# HomeLight_230722.net
KiCad netlist of a schematic drawn in Altium Designer
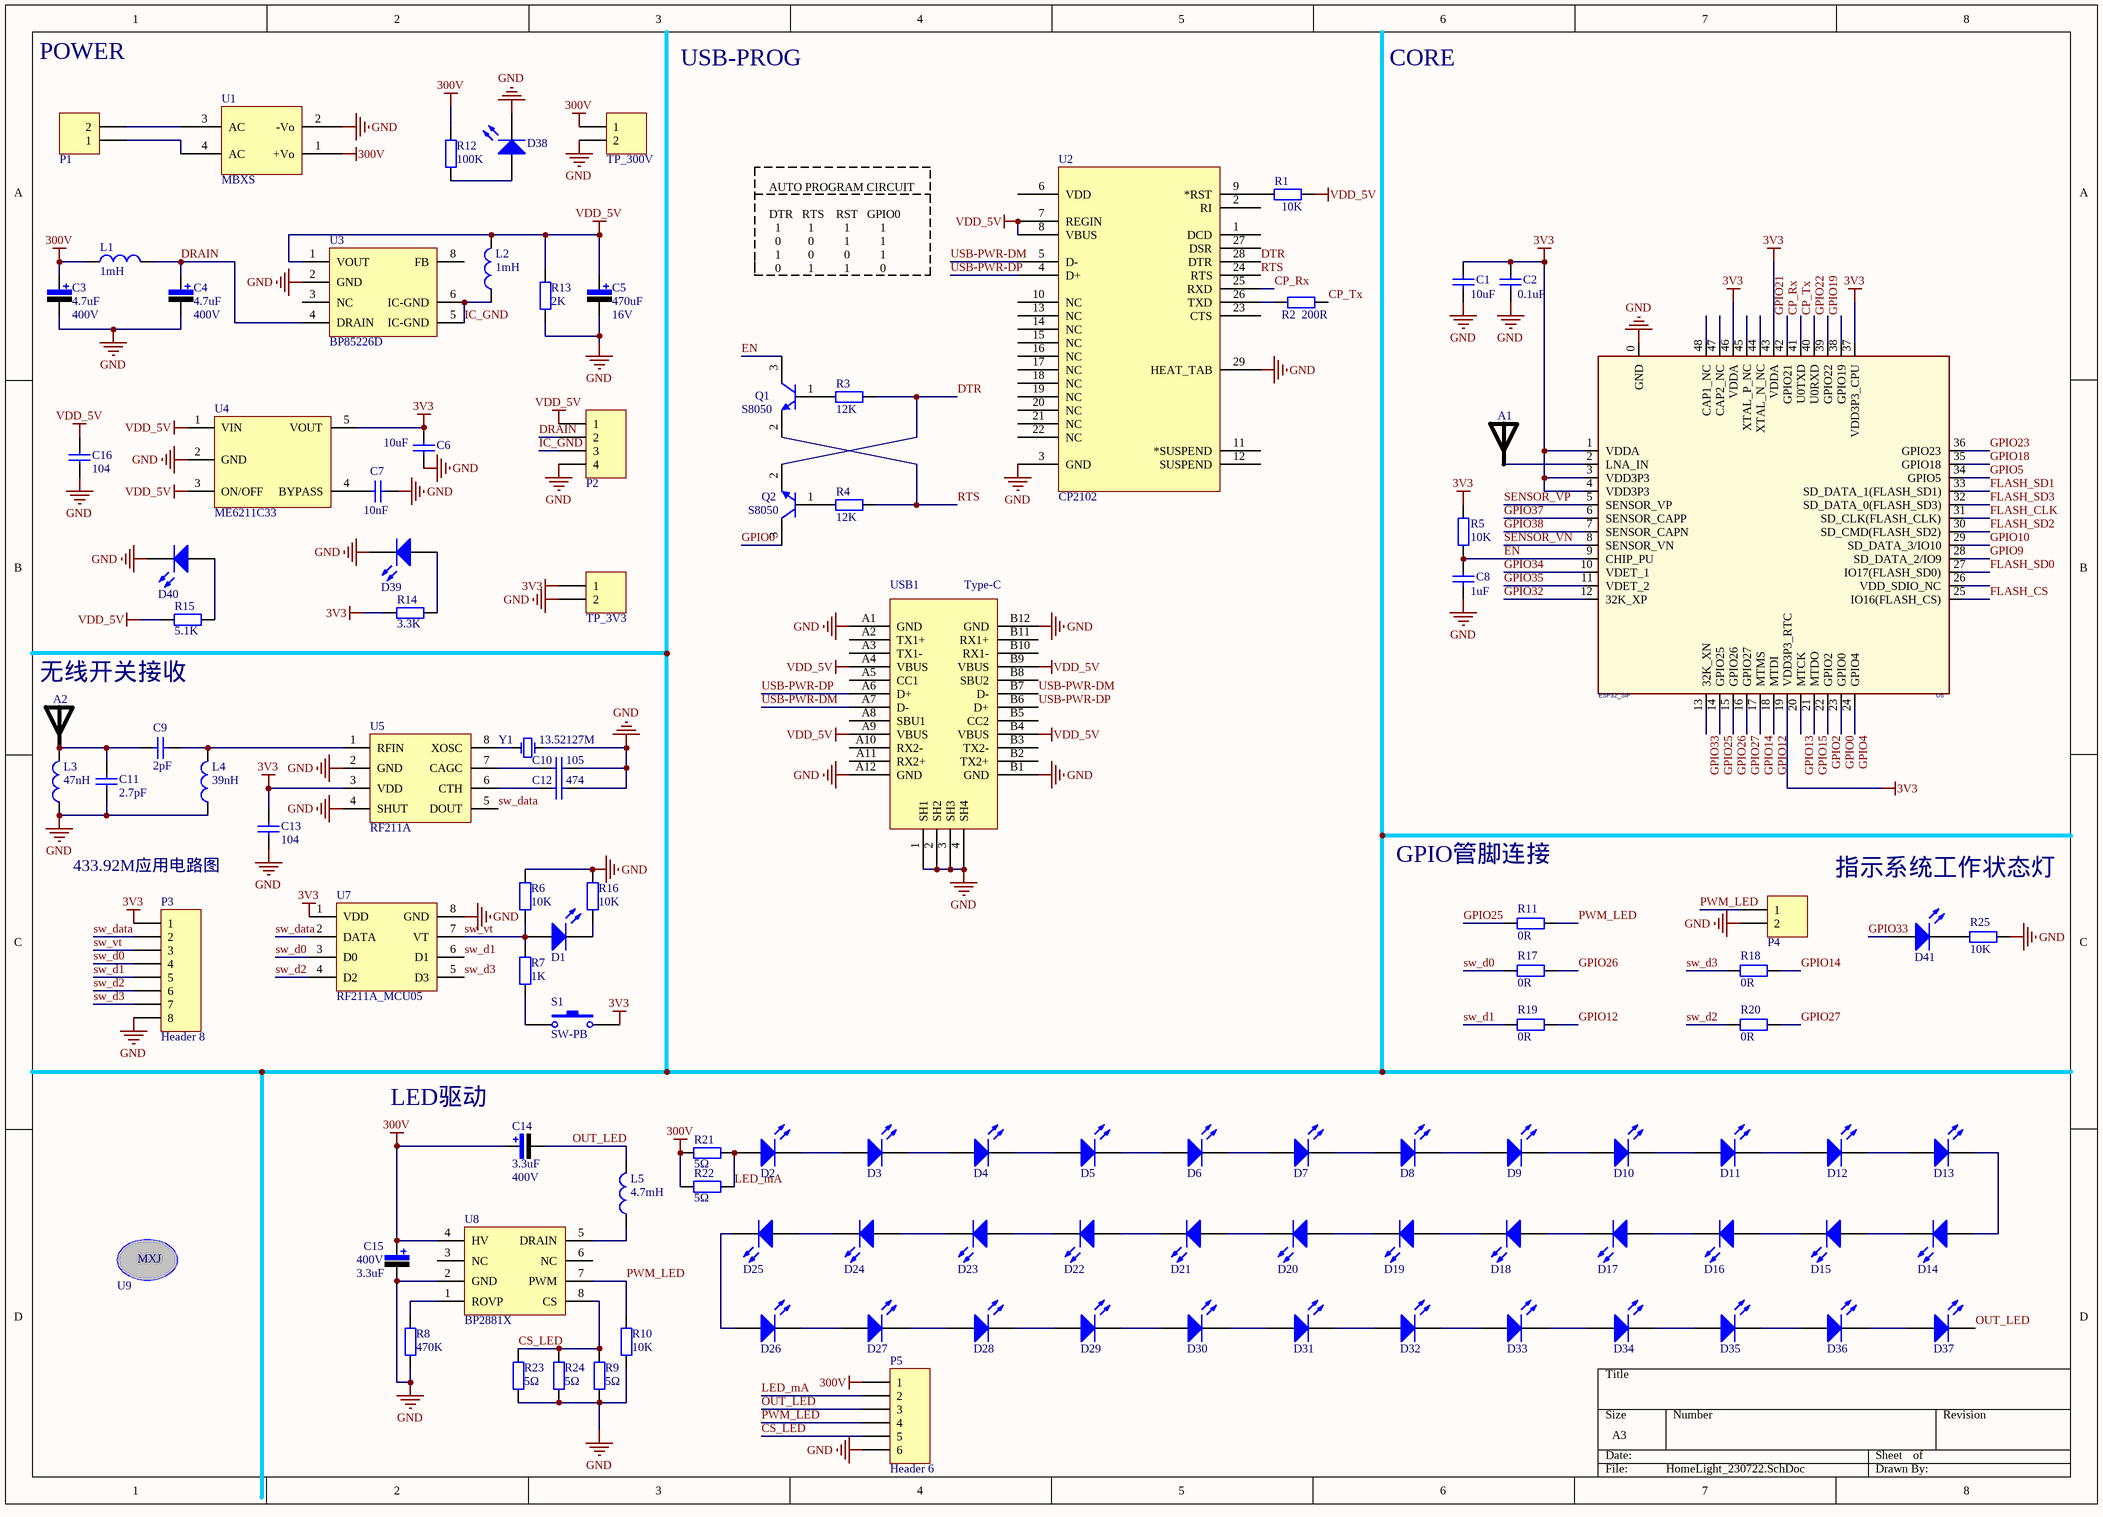
[diagram p0: HomeLight_230722.SchDoc]

(export (version "E")
  (design (tool "Eeschema 10.0.6"))
  (components
    (comp (ref "A1")
      (value "ANT")
      (footprint "ANT5020R2400")
      (libsource (lib "PCBSchlib_SEU_RobotLab") (part "ANT"))
    )
    (comp (ref "A2")
      (value "ANT")
      (footprint "PCBPcblib_SEU_RobotLab:ANT15030R433")
      (libsource (lib "PCBSchlib_SEU_RobotLab") (part "ANT"))
    )
    (comp (ref "C1")
      (value "10uF")
      (footprint "0603-2")
      (description "无极性电容")
      (fields (field (name "PUBLISHER") "Altium Limited"))
      (libsource (lib "PCBSchlib_SEU_RobotLab") (part "Cap"))
    )
    (comp (ref "C2")
      (value "0.1uF")
      (footprint "0603-2")
      (description "无极性电容")
      (fields (field (name "PUBLISHER") "Altium Limited"))
      (libsource (lib "PCBSchlib_SEU_RobotLab") (part "Cap"))
    )
    (comp (ref "C3")
      (value "4.7uF")
      (footprint "SMD-EC-F8")
      (description "极性电解电容")
      (fields
        (field (name "VOL") "400V")
        (field (name "Comment") "Cap Pol")
        (field (name "PUBLISHER") "Altium Limited")
      )
      (libsource (lib "PCBSchlib_SEU_RobotLab") (part "Cap Pol"))
    )
    (comp (ref "C4")
      (value "4.7uF")
      (footprint "SMD-EC-F8")
      (description "极性电解电容")
      (fields
        (field (name "VOL") "400V")
        (field (name "Comment") "Cap Pol")
        (field (name "PUBLISHER") "Altium Limited")
      )
      (libsource (lib "PCBSchlib_SEU_RobotLab") (part "Cap Pol"))
    )
    (comp (ref "C5")
      (value "470uF")
      (footprint "SMD-EC-F8")
      (description "极性电解电容")
      (fields
        (field (name "VOL") "16V")
        (field (name "Comment") "Cap Pol")
        (field (name "PUBLISHER") "Altium Limited")
      )
      (libsource (lib "PCBSchlib_SEU_RobotLab") (part "Cap Pol"))
    )
    (comp (ref "C6")
      (value "10uF")
      (footprint "0603-2")
      (description "无极性电容")
      (fields (field (name "PUBLISHER") "Altium Limited"))
      (libsource (lib "PCBSchlib_SEU_RobotLab") (part "Cap"))
    )
    (comp (ref "C7")
      (value "10nF")
      (footprint "0603-2")
      (description "无极性电容")
      (fields (field (name "PUBLISHER") "Altium Limited"))
      (libsource (lib "PCBSchlib_SEU_RobotLab") (part "Cap"))
    )
    (comp (ref "C8")
      (value "1uF")
      (footprint "0603-2")
      (description "无极性电容")
      (fields (field (name "PUBLISHER") "Altium Limited"))
      (libsource (lib "PCBSchlib_SEU_RobotLab") (part "Cap"))
    )
    (comp (ref "C9")
      (value "2pF")
      (footprint "0603-2")
      (description "无极性电容")
      (fields (field (name "Comment") "Cap") (field (name "PUBLISHER") "Altium Limited"))
      (libsource (lib "PCBSchlib_SEU_RobotLab") (part "Cap"))
    )
    (comp (ref "C10")
      (value "105")
      (footprint "0603-2")
      (description "无极性电容")
      (fields (field (name "Comment") "Cap") (field (name "PUBLISHER") "Altium Limited"))
      (libsource (lib "PCBSchlib_SEU_RobotLab") (part "Cap"))
    )
    (comp (ref "C11")
      (value "2.7pF")
      (footprint "0603-2")
      (description "无极性电容")
      (fields (field (name "Comment") "Cap") (field (name "PUBLISHER") "Altium Limited"))
      (libsource (lib "PCBSchlib_SEU_RobotLab") (part "Cap"))
    )
    (comp (ref "C12")
      (value "474")
      (footprint "0603-2")
      (description "无极性电容")
      (fields (field (name "Comment") "Cap") (field (name "PUBLISHER") "Altium Limited"))
      (libsource (lib "PCBSchlib_SEU_RobotLab") (part "Cap"))
    )
    (comp (ref "C13")
      (value "104")
      (footprint "0603-2")
      (description "无极性电容")
      (fields (field (name "Comment") "Cap") (field (name "PUBLISHER") "Altium Limited"))
      (libsource (lib "PCBSchlib_SEU_RobotLab") (part "Cap"))
    )
    (comp (ref "C14")
      (value "3.3uF")
      (footprint "SMD-EC-F8")
      (description "极性电解电容")
      (fields
        (field (name "VOL") "400V")
        (field (name "Comment") "Cap Pol")
        (field (name "PUBLISHER") "Altium Limited")
      )
      (libsource (lib "") (part "Cap Pol_1"))
    )
    (comp (ref "C15")
      (value "3.3uF")
      (footprint "SMD-EC-F8")
      (description "极性电解电容")
      (fields
        (field (name "VOL") "400V")
        (field (name "Comment") "Cap Pol")
        (field (name "PUBLISHER") "Altium Limited")
      )
      (libsource (lib "PCBSchlib_SEU_RobotLab") (part "Cap Pol"))
    )
    (comp (ref "C16")
      (value "104")
      (footprint "0603-2")
      (description "无极性电容")
      (fields (field (name "Comment") "Cap") (field (name "PUBLISHER") "Altium Limited"))
      (libsource (lib "PCBSchlib_SEU_RobotLab") (part "Cap"))
    )
    (comp (ref "D1")
      (value "LED0")
      (footprint "LED_0603")
      (description "发光二极管")
      (fields (field (name "PUBLISHER") "Altium Limited"))
      (libsource (lib "PCBSchlib_SEU_RobotLab") (part "LED0"))
    )
    (comp (ref "D2")
      (value "LED0")
      (footprint "PCBPcblib_SEU_RobotLab:LED-5730")
      (description "发光二极管")
      (fields (field (name "PUBLISHER") "Altium Limited"))
      (libsource (lib "PCBSchlib_SEU_RobotLab") (part "LED0"))
    )
    (comp (ref "D3")
      (value "LED0")
      (footprint "PCBPcblib_SEU_RobotLab:LED-5730")
      (description "发光二极管")
      (fields (field (name "PUBLISHER") "Altium Limited"))
      (libsource (lib "PCBSchlib_SEU_RobotLab") (part "LED0"))
    )
    (comp (ref "D4")
      (value "LED0")
      (footprint "PCBPcblib_SEU_RobotLab:LED-5730")
      (description "发光二极管")
      (fields (field (name "PUBLISHER") "Altium Limited"))
      (libsource (lib "PCBSchlib_SEU_RobotLab") (part "LED0"))
    )
    (comp (ref "D5")
      (value "LED0")
      (footprint "PCBPcblib_SEU_RobotLab:LED-5730")
      (description "发光二极管")
      (fields (field (name "PUBLISHER") "Altium Limited"))
      (libsource (lib "PCBSchlib_SEU_RobotLab") (part "LED0"))
    )
    (comp (ref "D6")
      (value "LED0")
      (footprint "PCBPcblib_SEU_RobotLab:LED-5730")
      (description "发光二极管")
      (fields (field (name "PUBLISHER") "Altium Limited"))
      (libsource (lib "PCBSchlib_SEU_RobotLab") (part "LED0"))
    )
    (comp (ref "D7")
      (value "LED0")
      (footprint "PCBPcblib_SEU_RobotLab:LED-5730")
      (description "发光二极管")
      (fields (field (name "PUBLISHER") "Altium Limited"))
      (libsource (lib "PCBSchlib_SEU_RobotLab") (part "LED0"))
    )
    (comp (ref "D8")
      (value "LED0")
      (footprint "PCBPcblib_SEU_RobotLab:LED-5730")
      (description "发光二极管")
      (fields (field (name "PUBLISHER") "Altium Limited"))
      (libsource (lib "PCBSchlib_SEU_RobotLab") (part "LED0"))
    )
    (comp (ref "D9")
      (value "LED0")
      (footprint "PCBPcblib_SEU_RobotLab:LED-5730")
      (description "发光二极管")
      (fields (field (name "PUBLISHER") "Altium Limited"))
      (libsource (lib "PCBSchlib_SEU_RobotLab") (part "LED0"))
    )
    (comp (ref "D10")
      (value "LED0")
      (footprint "PCBPcblib_SEU_RobotLab:LED-5730")
      (description "发光二极管")
      (fields (field (name "PUBLISHER") "Altium Limited"))
      (libsource (lib "PCBSchlib_SEU_RobotLab") (part "LED0"))
    )
    (comp (ref "D11")
      (value "LED0")
      (footprint "PCBPcblib_SEU_RobotLab:LED-5730")
      (description "发光二极管")
      (fields (field (name "PUBLISHER") "Altium Limited"))
      (libsource (lib "PCBSchlib_SEU_RobotLab") (part "LED0"))
    )
    (comp (ref "D12")
      (value "LED0")
      (footprint "PCBPcblib_SEU_RobotLab:LED-5730")
      (description "发光二极管")
      (fields (field (name "PUBLISHER") "Altium Limited"))
      (libsource (lib "PCBSchlib_SEU_RobotLab") (part "LED0"))
    )
    (comp (ref "D13")
      (value "LED0")
      (footprint "PCBPcblib_SEU_RobotLab:LED-5730")
      (description "发光二极管")
      (fields (field (name "PUBLISHER") "Altium Limited"))
      (libsource (lib "PCBSchlib_SEU_RobotLab") (part "LED0"))
    )
    (comp (ref "D14")
      (value "LED0")
      (footprint "PCBPcblib_SEU_RobotLab:LED-5730")
      (description "发光二极管")
      (fields (field (name "PUBLISHER") "Altium Limited"))
      (libsource (lib "PCBSchlib_SEU_RobotLab") (part "LED0"))
    )
    (comp (ref "D15")
      (value "LED0")
      (footprint "PCBPcblib_SEU_RobotLab:LED-5730")
      (description "发光二极管")
      (fields (field (name "PUBLISHER") "Altium Limited"))
      (libsource (lib "PCBSchlib_SEU_RobotLab") (part "LED0"))
    )
    (comp (ref "D16")
      (value "LED0")
      (footprint "PCBPcblib_SEU_RobotLab:LED-5730")
      (description "发光二极管")
      (fields (field (name "PUBLISHER") "Altium Limited"))
      (libsource (lib "PCBSchlib_SEU_RobotLab") (part "LED0"))
    )
    (comp (ref "D17")
      (value "LED0")
      (footprint "PCBPcblib_SEU_RobotLab:LED-5730")
      (description "发光二极管")
      (fields (field (name "PUBLISHER") "Altium Limited"))
      (libsource (lib "PCBSchlib_SEU_RobotLab") (part "LED0"))
    )
    (comp (ref "D18")
      (value "LED0")
      (footprint "PCBPcblib_SEU_RobotLab:LED-5730")
      (description "发光二极管")
      (fields (field (name "PUBLISHER") "Altium Limited"))
      (libsource (lib "PCBSchlib_SEU_RobotLab") (part "LED0"))
    )
    (comp (ref "D19")
      (value "LED0")
      (footprint "PCBPcblib_SEU_RobotLab:LED-5730")
      (description "发光二极管")
      (fields (field (name "PUBLISHER") "Altium Limited"))
      (libsource (lib "PCBSchlib_SEU_RobotLab") (part "LED0"))
    )
    (comp (ref "D20")
      (value "LED0")
      (footprint "PCBPcblib_SEU_RobotLab:LED-5730")
      (description "发光二极管")
      (fields (field (name "PUBLISHER") "Altium Limited"))
      (libsource (lib "PCBSchlib_SEU_RobotLab") (part "LED0"))
    )
    (comp (ref "D21")
      (value "LED0")
      (footprint "PCBPcblib_SEU_RobotLab:LED-5730")
      (description "发光二极管")
      (fields (field (name "PUBLISHER") "Altium Limited"))
      (libsource (lib "PCBSchlib_SEU_RobotLab") (part "LED0"))
    )
    (comp (ref "D22")
      (value "LED0")
      (footprint "PCBPcblib_SEU_RobotLab:LED-5730")
      (description "发光二极管")
      (fields (field (name "PUBLISHER") "Altium Limited"))
      (libsource (lib "PCBSchlib_SEU_RobotLab") (part "LED0"))
    )
    (comp (ref "D23")
      (value "LED0")
      (footprint "PCBPcblib_SEU_RobotLab:LED-5730")
      (description "发光二极管")
      (fields (field (name "PUBLISHER") "Altium Limited"))
      (libsource (lib "PCBSchlib_SEU_RobotLab") (part "LED0"))
    )
    (comp (ref "D24")
      (value "LED0")
      (footprint "PCBPcblib_SEU_RobotLab:LED-5730")
      (description "发光二极管")
      (fields (field (name "PUBLISHER") "Altium Limited"))
      (libsource (lib "PCBSchlib_SEU_RobotLab") (part "LED0"))
    )
    (comp (ref "D25")
      (value "LED0")
      (footprint "PCBPcblib_SEU_RobotLab:LED-5730")
      (description "发光二极管")
      (fields (field (name "PUBLISHER") "Altium Limited"))
      (libsource (lib "PCBSchlib_SEU_RobotLab") (part "LED0"))
    )
    (comp (ref "D26")
      (value "LED0")
      (footprint "PCBPcblib_SEU_RobotLab:LED-5730")
      (description "发光二极管")
      (fields (field (name "PUBLISHER") "Altium Limited"))
      (libsource (lib "PCBSchlib_SEU_RobotLab") (part "LED0"))
    )
    (comp (ref "D27")
      (value "LED0")
      (footprint "PCBPcblib_SEU_RobotLab:LED-5730")
      (description "发光二极管")
      (fields (field (name "PUBLISHER") "Altium Limited"))
      (libsource (lib "PCBSchlib_SEU_RobotLab") (part "LED0"))
    )
    (comp (ref "D28")
      (value "LED0")
      (footprint "PCBPcblib_SEU_RobotLab:LED-5730")
      (description "发光二极管")
      (fields (field (name "PUBLISHER") "Altium Limited"))
      (libsource (lib "PCBSchlib_SEU_RobotLab") (part "LED0"))
    )
    (comp (ref "D29")
      (value "LED0")
      (footprint "PCBPcblib_SEU_RobotLab:LED-5730")
      (description "发光二极管")
      (fields (field (name "PUBLISHER") "Altium Limited"))
      (libsource (lib "PCBSchlib_SEU_RobotLab") (part "LED0"))
    )
    (comp (ref "D30")
      (value "LED0")
      (footprint "PCBPcblib_SEU_RobotLab:LED-5730")
      (description "发光二极管")
      (fields (field (name "PUBLISHER") "Altium Limited"))
      (libsource (lib "PCBSchlib_SEU_RobotLab") (part "LED0"))
    )
    (comp (ref "D31")
      (value "LED0")
      (footprint "PCBPcblib_SEU_RobotLab:LED-5730")
      (description "发光二极管")
      (fields (field (name "PUBLISHER") "Altium Limited"))
      (libsource (lib "PCBSchlib_SEU_RobotLab") (part "LED0"))
    )
    (comp (ref "D32")
      (value "LED0")
      (footprint "PCBPcblib_SEU_RobotLab:LED-5730")
      (description "发光二极管")
      (fields (field (name "PUBLISHER") "Altium Limited"))
      (libsource (lib "PCBSchlib_SEU_RobotLab") (part "LED0"))
    )
    (comp (ref "D33")
      (value "LED0")
      (footprint "PCBPcblib_SEU_RobotLab:LED-5730")
      (description "发光二极管")
      (fields (field (name "PUBLISHER") "Altium Limited"))
      (libsource (lib "PCBSchlib_SEU_RobotLab") (part "LED0"))
    )
    (comp (ref "D34")
      (value "LED0")
      (footprint "PCBPcblib_SEU_RobotLab:LED-5730")
      (description "发光二极管")
      (fields (field (name "PUBLISHER") "Altium Limited"))
      (libsource (lib "PCBSchlib_SEU_RobotLab") (part "LED0"))
    )
    (comp (ref "D35")
      (value "LED0")
      (footprint "PCBPcblib_SEU_RobotLab:LED-5730")
      (description "发光二极管")
      (fields (field (name "PUBLISHER") "Altium Limited"))
      (libsource (lib "PCBSchlib_SEU_RobotLab") (part "LED0"))
    )
    (comp (ref "D36")
      (value "LED0")
      (footprint "PCBPcblib_SEU_RobotLab:LED-5730")
      (description "发光二极管")
      (fields (field (name "PUBLISHER") "Altium Limited"))
      (libsource (lib "PCBSchlib_SEU_RobotLab") (part "LED0"))
    )
    (comp (ref "D37")
      (value "LED0")
      (footprint "PCBPcblib_SEU_RobotLab:LED-5730")
      (description "发光二极管")
      (fields (field (name "PUBLISHER") "Altium Limited"))
      (libsource (lib "PCBSchlib_SEU_RobotLab") (part "LED0"))
    )
    (comp (ref "D38")
      (value "LED0")
      (footprint "LED_0603")
      (description "发光二极管")
      (fields (field (name "PUBLISHER") "Altium Limited"))
      (libsource (lib "PCBSchlib_SEU_RobotLab") (part "LED0"))
    )
    (comp (ref "D39")
      (value "LED0")
      (footprint "LED_0603")
      (description "发光二极管")
      (fields (field (name "PUBLISHER") "Altium Limited"))
      (libsource (lib "PCBSchlib_SEU_RobotLab") (part "LED0"))
    )
    (comp (ref "D40")
      (value "LED0")
      (footprint "LED_0603")
      (description "发光二极管")
      (fields (field (name "PUBLISHER") "Altium Limited"))
      (libsource (lib "PCBSchlib_SEU_RobotLab") (part "LED0"))
    )
    (comp (ref "D41")
      (value "LED0")
      (footprint "LED_0603")
      (description "发光二极管")
      (fields (field (name "PUBLISHER") "Altium Limited"))
      (libsource (lib "PCBSchlib_SEU_RobotLab") (part "LED0"))
    )
    (comp (ref "L1")
      (value "1mH")
      (footprint "PCBPcblib_SEU_RobotLab:CD54")
      (description "电感")
      (fields (field (name "Comment") "Inductor") (field (name "PUBLISHER") "Altium Limited"))
      (libsource (lib "PCBSchlib_SEU_RobotLab") (part "Inductor"))
    )
    (comp (ref "L2")
      (value "1mH")
      (footprint "PCBPcblib_SEU_RobotLab:CD54")
      (description "电感")
      (fields (field (name "Comment") "Inductor") (field (name "PUBLISHER") "Altium Limited"))
      (libsource (lib "PCBSchlib_SEU_RobotLab") (part "Inductor"))
    )
    (comp (ref "L3")
      (value "47nH")
      (footprint "PCBPcblib_SEU_RobotLab:0603-1")
      (description "电感")
      (fields (field (name "Comment") "Inductor") (field (name "PUBLISHER") "Altium Limited"))
      (libsource (lib "PCBSchlib_SEU_RobotLab") (part "Inductor"))
    )
    (comp (ref "L4")
      (value "39nH")
      (footprint "PCBPcblib_SEU_RobotLab:0603-1")
      (description "电感")
      (fields (field (name "Comment") "Inductor") (field (name "PUBLISHER") "Altium Limited"))
      (libsource (lib "PCBSchlib_SEU_RobotLab") (part "Inductor"))
    )
    (comp (ref "L5")
      (value "4.7mH")
      (footprint "PCBPcblib_SEU_RobotLab:CD54")
      (description "电感")
      (fields (field (name "Comment") "Inductor") (field (name "PUBLISHER") "Altium Limited"))
      (libsource (lib "PCBSchlib_SEU_RobotLab") (part "Inductor"))
    )
    (comp (ref "P1")
      (value "Header 2")
      (footprint "PCBPcblib_SEU_RobotLab:HDR2X1_焊接版")
      (description "接插件")
      (fields (field (name "PUBLISHER") "Altium Limited"))
      (libsource (lib "") (part "Header 2_1"))
    )
    (comp (ref "P2")
      (value "Header 4")
      (footprint "HDR4X1_2.54")
      (description "接插件")
      (fields (field (name "PUBLISHER") "Altium Limited"))
      (libsource (lib "PCBSchlib_SEU_RobotLab") (part "Header 4"))
    )
    (comp (ref "P3")
      (value "Header 8")
      (footprint "HDR8X1_2.54")
      (description "Header, 8-Pin")
      (fields (field (name "PUBLISHER") "Altium Limited"))
      (libsource (lib "PCBSchlib_SEU_RobotLab") (part "Header 8"))
    )
    (comp (ref "P4")
      (value "Header 2")
      (footprint "HDR2X1_2.54")
      (description "接插件")
      (fields (field (name "PUBLISHER") "Altium Limited"))
      (libsource (lib "PCBSchlib_SEU_RobotLab") (part "Header 2"))
    )
    (comp (ref "P5")
      (value "Header 6")
      (footprint "HDR6X1_2.54")
      (description "接插件")
      (fields (field (name "PUBLISHER") "Altium Limited"))
      (libsource (lib "PCBSchlib_SEU_RobotLab") (part "Header 6"))
    )
    (comp (ref "Q1")
      (value "S8050")
      (footprint "PCBPcblib_SEU_RobotLab:SOT-23")
      (description "NPN三极管")
      (fields (field (name "PUBLISHER") "Altium Limited"))
      (libsource (lib "PCBSchlib_SEU_RobotLab") (part "Triode-NPN"))
    )
    (comp (ref "Q2")
      (value "S8050")
      (footprint "PCBPcblib_SEU_RobotLab:SOT-23")
      (description "NPN三极管")
      (fields (field (name "PUBLISHER") "Altium Limited"))
      (libsource (lib "PCBSchlib_SEU_RobotLab") (part "Triode-NPN"))
    )
    (comp (ref "R1")
      (value "10K")
      (footprint "0603-1")
      (description "贴片电阻")
      (fields (field (name "PUBLISHER") "Altium Limited"))
      (libsource (lib "") (part "Res1_1"))
    )
    (comp (ref "R2")
      (value "200R")
      (footprint "0603-1")
      (description "贴片电阻")
      (fields (field (name "PUBLISHER") "Altium Limited"))
      (libsource (lib "") (part "Res1_1"))
    )
    (comp (ref "R3")
      (value "12K")
      (footprint "0603-1")
      (description "贴片电阻")
      (fields (field (name "PUBLISHER") "Altium Limited"))
      (libsource (lib "") (part "Res1_1"))
    )
    (comp (ref "R4")
      (value "12K")
      (footprint "0603-1")
      (description "贴片电阻")
      (fields (field (name "PUBLISHER") "Altium Limited"))
      (libsource (lib "") (part "Res1_1"))
    )
    (comp (ref "R5")
      (value "10K")
      (footprint "0603-1")
      (description "贴片电阻")
      (fields (field (name "PUBLISHER") "Altium Limited"))
      (libsource (lib "") (part "Res1_2"))
    )
    (comp (ref "R6")
      (value "10K")
      (footprint "0603-1")
      (description "贴片电阻")
      (fields (field (name "Comment") "Res1") (field (name "PUBLISHER") "Altium Limited"))
      (libsource (lib "PCBSchlib_SEU_RobotLab") (part "Res1"))
    )
    (comp (ref "R7")
      (value "1K")
      (footprint "0603-1")
      (description "贴片电阻")
      (fields (field (name "Comment") "Res1") (field (name "PUBLISHER") "Altium Limited"))
      (libsource (lib "PCBSchlib_SEU_RobotLab") (part "Res1"))
    )
    (comp (ref "R8")
      (value "470K")
      (footprint "0603-1")
      (description "贴片电阻")
      (fields (field (name "Comment") "Res1") (field (name "PUBLISHER") "Altium Limited"))
      (libsource (lib "PCBSchlib_SEU_RobotLab") (part "Res1"))
    )
    (comp (ref "R9")
      (value "5Ω")
      (footprint "0603-1")
      (description "贴片电阻")
      (fields (field (name "Comment") "Res1") (field (name "PUBLISHER") "Altium Limited"))
      (libsource (lib "PCBSchlib_SEU_RobotLab") (part "Res1"))
    )
    (comp (ref "R10")
      (value "10K")
      (footprint "0603-1")
      (description "贴片电阻")
      (fields (field (name "Comment") "Res1") (field (name "PUBLISHER") "Altium Limited"))
      (libsource (lib "PCBSchlib_SEU_RobotLab") (part "Res1"))
    )
    (comp (ref "R11")
      (value "0R")
      (footprint "0603-1")
      (description "贴片电阻")
      (fields (field (name "Comment") "Res1") (field (name "PUBLISHER") "Altium Limited"))
      (libsource (lib "") (part "Res1_1"))
    )
    (comp (ref "R12")
      (value "100K")
      (footprint "0603-1")
      (description "贴片电阻")
      (fields (field (name "Comment") "12K") (field (name "PUBLISHER") "Altium Limited"))
      (libsource (lib "PCBSchlib_SEU_RobotLab") (part "Res1"))
    )
    (comp (ref "R13")
      (value "2K")
      (footprint "0603-1")
      (description "贴片电阻")
      (fields (field (name "Comment") "12K") (field (name "PUBLISHER") "Altium Limited"))
      (libsource (lib "") (part "Res1_2"))
    )
    (comp (ref "R14")
      (value "3.3K")
      (footprint "0603-1")
      (description "贴片电阻")
      (fields (field (name "Comment") "12K") (field (name "PUBLISHER") "Altium Limited"))
      (libsource (lib "") (part "Res1_1"))
    )
    (comp (ref "R15")
      (value "5.1K")
      (footprint "0603-1")
      (description "贴片电阻")
      (fields (field (name "Comment") "12K") (field (name "PUBLISHER") "Altium Limited"))
      (libsource (lib "") (part "Res1_1"))
    )
    (comp (ref "R16")
      (value "10K")
      (footprint "0603-1")
      (description "贴片电阻")
      (fields (field (name "Comment") "Res1") (field (name "PUBLISHER") "Altium Limited"))
      (libsource (lib "PCBSchlib_SEU_RobotLab") (part "Res1"))
    )
    (comp (ref "R17")
      (value "0R")
      (footprint "0603-1")
      (description "贴片电阻")
      (fields (field (name "Comment") "Res1") (field (name "PUBLISHER") "Altium Limited"))
      (libsource (lib "") (part "Res1_1"))
    )
    (comp (ref "R18")
      (value "0R")
      (footprint "0603-1")
      (description "贴片电阻")
      (fields (field (name "Comment") "Res1") (field (name "PUBLISHER") "Altium Limited"))
      (libsource (lib "") (part "Res1_1"))
    )
    (comp (ref "R19")
      (value "0R")
      (footprint "0603-1")
      (description "贴片电阻")
      (fields (field (name "Comment") "Res1") (field (name "PUBLISHER") "Altium Limited"))
      (libsource (lib "") (part "Res1_1"))
    )
    (comp (ref "R20")
      (value "0R")
      (footprint "0603-1")
      (description "贴片电阻")
      (fields (field (name "Comment") "Res1") (field (name "PUBLISHER") "Altium Limited"))
      (libsource (lib "") (part "Res1_1"))
    )
    (comp (ref "R21")
      (value "5Ω")
      (footprint "0603-1")
      (description "贴片电阻")
      (fields (field (name "Comment") "Res1") (field (name "PUBLISHER") "Altium Limited"))
      (libsource (lib "") (part "Res1_1"))
    )
    (comp (ref "R22")
      (value "5Ω")
      (footprint "0603-1")
      (description "贴片电阻")
      (fields (field (name "Comment") "Res1") (field (name "PUBLISHER") "Altium Limited"))
      (libsource (lib "") (part "Res1_1"))
    )
    (comp (ref "R23")
      (value "5Ω")
      (footprint "0603-1")
      (description "贴片电阻")
      (fields (field (name "Comment") "Res1") (field (name "PUBLISHER") "Altium Limited"))
      (libsource (lib "PCBSchlib_SEU_RobotLab") (part "Res1"))
    )
    (comp (ref "R24")
      (value "5Ω")
      (footprint "0603-1")
      (description "贴片电阻")
      (fields (field (name "Comment") "Res1") (field (name "PUBLISHER") "Altium Limited"))
      (libsource (lib "PCBSchlib_SEU_RobotLab") (part "Res1"))
    )
    (comp (ref "R25")
      (value "10K")
      (footprint "0603-1")
      (description "贴片电阻")
      (fields (field (name "Comment") "Res1") (field (name "PUBLISHER") "Altium Limited"))
      (libsource (lib "") (part "Res1_1"))
    )
    (comp (ref "S1")
      (value "SW-PB")
      (footprint "SW_PB2_A1")
      (description "微动开关")
      (fields (field (name "PUBLISHER") "Altium Limited"))
      (libsource (lib "PCBSchlib_SEU_RobotLab") (part "SW-PB"))
    )
    (comp (ref "TP_3V3")
      (value "Header 2")
      (footprint "HDR2X1_2.54")
      (description "接插件")
      (fields (field (name "PUBLISHER") "Altium Limited"))
      (libsource (lib "PCBSchlib_SEU_RobotLab") (part "Header 2"))
    )
    (comp (ref "TP_300V")
      (value "Header 2")
      (footprint "HDR2X1_2.54")
      (description "接插件")
      (fields (field (name "PUBLISHER") "Altium Limited"))
      (libsource (lib "PCBSchlib_SEU_RobotLab") (part "Header 2"))
    )
    (comp (ref "U1")
      (value "MBXS")
      (footprint "PCBPcblib_SEU_RobotLab:MBXS")
      (description "整流桥")
      (libsource (lib "PCBSchlib_SEU_RobotLab") (part "MBXS"))
    )
    (comp (ref "U2")
      (value "CP2102")
      (footprint "QFN-28")
      (description "USB转TTL")
      (libsource (lib "mLib") (part "CP2102"))
    )
    (comp (ref "U3")
      (value "BP85226D")
      (footprint "PCBPcblib_SEU_RobotLab:BP85226-BP2881")
      (description "开关电源驱动芯片")
      (libsource (lib "PCBSchlib_SEU_RobotLab") (part "BP85226"))
    )
    (comp (ref "U4")
      (value "ME6211C33")
      (footprint "SOT23-5")
      (description "LDO")
      (libsource (lib "PCBSchlib_SEU_RobotLab") (part "LP2992"))
    )
    (comp (ref "U5")
      (value "RF211A")
      (footprint "PCBPcblib_SEU_RobotLab:SOIC-8")
      (description "315M无线接收芯片")
      (libsource (lib "PCBSchlib_SEU_RobotLab") (part "RF211A"))
    )
    (comp (ref "U6")
      (value "ESP32_SIP")
      (footprint "QFN-48_7X7")
      (libsource (lib "PCBSchlib_SEU_RobotLab") (part "ESP32-PICO"))
    )
    (comp (ref "U7")
      (value "RF211A_MCU05")
      (footprint "PCBPcblib_SEU_RobotLab:SOIC-8")
      (description "无线接收芯片的解码芯片")
      (libsource (lib "PCBSchlib_SEU_RobotLab") (part "RF211A_MCU05"))
    )
    (comp (ref "U8")
      (value "BP2881X")
      (footprint "PCBPcblib_SEU_RobotLab:BP85226-BP2881")
      (description "PWM调光非隔离降压型LED恒流驱动芯片")
      (libsource (lib "PCBSchlib_SEU_RobotLab") (part "BP2881X"))
    )
    (comp (ref "U9")
      (value "logo_MXJ")
      (footprint "PCBPcblib_SEU_RobotLab:logo_MXJ")
      (libsource (lib "PCBSchlib_SEU_RobotLab") (part "logo_MXJ"))
    )
    (comp (ref "USB1")
      (value "Type-C")
      (footprint "Type-C-TOP")
      (libsource (lib "PCBSchlib_SEU_RobotLab") (part "USB-Type-C-TOP"))
    )
    (comp (ref "Y1")
      (value "13.52127M")
      (footprint "X-SM49")
      (description "晶振")
      (fields (field (name "Comment") "XTAL") (field (name "PUBLISHER") "Altium Limited"))
      (libsource (lib "PCBSchlib_SEU_RobotLab") (part "XTAL"))
    )
  )
  (nets
    (net (code "1") (name "/CP_Rx") (class "Default")
      (node (ref "U2") (pin "25") (pinfunction "RXD_25") (pintype "passive"))
      (node (ref "U6") (pin "41") (pinfunction "U0TXD_41") (pintype "power_in"))
    )
    (net (code "2") (name "/CP_Tx") (class "Default")
      (node (ref "R2") (pin "1") (pinfunction "1_1") (pintype "passive"))
      (node (ref "U6") (pin "40") (pinfunction "U0RXD_40") (pintype "power_in"))
    )
    (net (code "3") (name "/CS_LED") (class "Default")
      (node (ref "P5") (pin "5") (pinfunction "5_5") (pintype "passive"))
      (node (ref "R23") (pin "2") (pinfunction "2_2") (pintype "passive"))
      (node (ref "R24") (pin "2") (pinfunction "2_2") (pintype "passive"))
      (node (ref "R9") (pin "2") (pinfunction "2_2") (pintype "passive"))
      (node (ref "U8") (pin "8") (pinfunction "CS_8") (pintype "passive"))
    )
    (net (code "4") (name "/DRAIN") (class "Default")
      (node (ref "C4") (pin "1") (pinfunction "1_1") (pintype "passive"))
      (node (ref "L1") (pin "2") (pinfunction "2_2") (pintype "passive"))
      (node (ref "P2") (pin "2") (pinfunction "2_2") (pintype "passive"))
      (node (ref "U3") (pin "4") (pinfunction "DRAIN_4") (pintype "passive"))
    )
    (net (code "5") (name "/DTR") (class "Default")
      (node (ref "Q2") (pin "2") (pinfunction "E_2") (pintype "passive"))
      (node (ref "R3") (pin "1") (pinfunction "1_1") (pintype "passive"))
      (node (ref "U2") (pin "28") (pinfunction "DTR_28") (pintype "passive"))
    )
    (net (code "6") (name "/EN") (class "Default")
      (node (ref "C8") (pin "1") (pinfunction "1_1") (pintype "passive"))
      (node (ref "Q1") (pin "3") (pinfunction "C_3") (pintype "passive"))
      (node (ref "R5") (pin "2") (pinfunction "2_2") (pintype "passive"))
      (node (ref "U6") (pin "9") (pinfunction "CHIP_PU_9") (pintype "passive"))
    )
    (net (code "7") (name "/FLASH_CLK") (class "Default")
      (node (ref "U6") (pin "31") (pinfunction "SD_CLK(FLASH_CLK)_31") (pintype "passive"))
    )
    (net (code "8") (name "/FLASH_CS") (class "Default")
      (node (ref "U6") (pin "25") (pinfunction "IO16(FLASH_CS)_25") (pintype "passive"))
    )
    (net (code "9") (name "/FLASH_SD0") (class "Default")
      (node (ref "U6") (pin "27") (pinfunction "IO17(FLASH_SD0)_27") (pintype "passive"))
    )
    (net (code "10") (name "/FLASH_SD1") (class "Default")
      (node (ref "U6") (pin "33") (pinfunction "SD_DATA_1(FLASH_SD1)_33") (pintype "passive"))
    )
    (net (code "11") (name "/FLASH_SD2") (class "Default")
      (node (ref "U6") (pin "30") (pinfunction "SD_CMD(FLASH_SD2)_30") (pintype "passive"))
    )
    (net (code "12") (name "/FLASH_SD3") (class "Default")
      (node (ref "U6") (pin "32") (pinfunction "SD_DATA_0(FLASH_SD3)_32") (pintype "passive"))
    )
    (net (code "13") (name "/GPIO0") (class "Default")
      (node (ref "Q2") (pin "3") (pinfunction "C_3") (pintype "passive"))
      (node (ref "U6") (pin "23") (pinfunction "GPIO0_23") (pintype "passive"))
    )
    (net (code "14") (name "/GPIO2") (class "Default")
      (node (ref "U6") (pin "22") (pinfunction "GPIO2_22") (pintype "passive"))
    )
    (net (code "15") (name "/GPIO4") (class "Default")
      (node (ref "U6") (pin "24") (pinfunction "GPIO4_24") (pintype "passive"))
    )
    (net (code "16") (name "/GPIO5") (class "Default")
      (node (ref "U6") (pin "34") (pinfunction "GPIO5_34") (pintype "passive"))
    )
    (net (code "17") (name "/GPIO9") (class "Default")
      (node (ref "U6") (pin "28") (pinfunction "SD_DATA_2/IO9_28") (pintype "passive"))
    )
    (net (code "18") (name "/GPIO10") (class "Default")
      (node (ref "U6") (pin "29") (pinfunction "SD_DATA_3/IO10_29") (pintype "passive"))
    )
    (net (code "19") (name "/GPIO12") (class "Default")
      (node (ref "R19") (pin "1") (pinfunction "1_1") (pintype "passive"))
      (node (ref "U6") (pin "18") (pinfunction "MTDI_18") (pintype "passive"))
    )
    (net (code "20") (name "/GPIO13") (class "Default")
      (node (ref "U6") (pin "20") (pinfunction "MTCK_20") (pintype "passive"))
    )
    (net (code "21") (name "/GPIO14") (class "Default")
      (node (ref "R18") (pin "1") (pinfunction "1_1") (pintype "passive"))
      (node (ref "U6") (pin "17") (pinfunction "MTMS_17") (pintype "passive"))
    )
    (net (code "22") (name "/GPIO15") (class "Default")
      (node (ref "U6") (pin "21") (pinfunction "MTDO_21") (pintype "passive"))
    )
    (net (code "23") (name "/GPIO18") (class "Default")
      (node (ref "U6") (pin "35") (pinfunction "GPIO18_35") (pintype "passive"))
    )
    (net (code "24") (name "/GPIO19") (class "Default")
      (node (ref "U6") (pin "38") (pinfunction "GPIO19_38") (pintype "passive"))
    )
    (net (code "25") (name "/GPIO21") (class "Default")
      (node (ref "U6") (pin "42") (pinfunction "GPIO21_42") (pintype "passive"))
    )
    (net (code "26") (name "/GPIO22") (class "Default")
      (node (ref "U6") (pin "39") (pinfunction "GPIO22_39") (pintype "passive"))
    )
    (net (code "27") (name "/GPIO23") (class "Default")
      (node (ref "U6") (pin "36") (pinfunction "GPIO23_36") (pintype "passive"))
    )
    (net (code "28") (name "/GPIO25") (class "Default")
      (node (ref "R11") (pin "2") (pinfunction "2_2") (pintype "passive"))
      (node (ref "U6") (pin "14") (pinfunction "GPIO25_14") (pintype "passive"))
    )
    (net (code "29") (name "/GPIO26") (class "Default")
      (node (ref "R17") (pin "1") (pinfunction "1_1") (pintype "passive"))
      (node (ref "U6") (pin "15") (pinfunction "GPIO26_15") (pintype "passive"))
    )
    (net (code "30") (name "/GPIO27") (class "Default")
      (node (ref "R20") (pin "1") (pinfunction "1_1") (pintype "passive"))
      (node (ref "U6") (pin "16") (pinfunction "GPIO27_16") (pintype "passive"))
    )
    (net (code "31") (name "/GPIO32") (class "Default")
      (node (ref "U6") (pin "12") (pinfunction "32K_XP_12") (pintype "passive"))
    )
    (net (code "32") (name "/GPIO33") (class "Default")
      (node (ref "D41") (pin "1") (pinfunction "A_1") (pintype "passive"))
      (node (ref "U6") (pin "13") (pinfunction "32K_XN_13") (pintype "passive"))
    )
    (net (code "33") (name "/GPIO34") (class "Default")
      (node (ref "U6") (pin "10") (pinfunction "VDET_1_10") (pintype "passive"))
    )
    (net (code "34") (name "/GPIO35") (class "Default")
      (node (ref "U6") (pin "11") (pinfunction "VDET_2_11") (pintype "passive"))
    )
    (net (code "35") (name "/GPIO37") (class "Default")
      (node (ref "U6") (pin "6") (pinfunction "SENSOR_CAPP_6") (pintype "passive"))
    )
    (net (code "36") (name "/GPIO38") (class "Default")
      (node (ref "U6") (pin "7") (pinfunction "SENSOR_CAPN_7") (pintype "passive"))
    )
    (net (code "37") (name "/IC_GND") (class "Default")
      (node (ref "L2") (pin "1") (pinfunction "1_1") (pintype "passive"))
      (node (ref "P2") (pin "3") (pinfunction "3_3") (pintype "passive"))
      (node (ref "U3") (pin "5") (pinfunction "IC-GND_5") (pintype "passive"))
      (node (ref "U3") (pin "6") (pinfunction "IC-GND_6") (pintype "passive"))
    )
    (net (code "38") (name "/LED_mA") (class "Default")
      (node (ref "D2") (pin "1") (pinfunction "A_1") (pintype "passive"))
      (node (ref "P5") (pin "2") (pinfunction "2_2") (pintype "passive"))
      (node (ref "R21") (pin "1") (pinfunction "1_1") (pintype "passive"))
      (node (ref "R22") (pin "1") (pinfunction "1_1") (pintype "passive"))
    )
    (net (code "39") (name "/OUT_LED") (class "Default")
      (node (ref "C14") (pin "2") (pinfunction "2_2") (pintype "passive"))
      (node (ref "D37") (pin "2") (pinfunction "K_2") (pintype "passive"))
      (node (ref "L5") (pin "2") (pinfunction "2_2") (pintype "passive"))
      (node (ref "P5") (pin "3") (pinfunction "3_3") (pintype "passive"))
    )
    (net (code "40") (name "/PWM_LED") (class "Default")
      (node (ref "P4") (pin "1") (pinfunction "1_1") (pintype "passive"))
      (node (ref "P5") (pin "4") (pinfunction "4_4") (pintype "passive"))
      (node (ref "R10") (pin "2") (pinfunction "2_2") (pintype "passive"))
      (node (ref "R11") (pin "1") (pinfunction "1_1") (pintype "passive"))
      (node (ref "U8") (pin "7") (pinfunction "PWM_7") (pintype "passive"))
    )
    (net (code "41") (name "/RTS") (class "Default")
      (node (ref "Q1") (pin "2") (pinfunction "E_2") (pintype "passive"))
      (node (ref "R4") (pin "1") (pinfunction "1_1") (pintype "passive"))
      (node (ref "U2") (pin "24") (pinfunction "RTS_24") (pintype "passive"))
    )
    (net (code "42") (name "/SENSOR_VN") (class "Default")
      (node (ref "U6") (pin "8") (pinfunction "SENSOR_VN_8") (pintype "passive"))
    )
    (net (code "43") (name "/SENSOR_VP") (class "Default")
      (node (ref "U6") (pin "5") (pinfunction "SENSOR_VP_5") (pintype "passive"))
    )
    (net (code "44") (name "/USB-PWR-DM") (class "Default")
      (node (ref "U2") (pin "5") (pinfunction "D-_5") (pintype "passive"))
      (node (ref "USB1") (pin "A7") (pinfunction "D-_A7") (pintype "passive"))
      (node (ref "USB1") (pin "B7") (pinfunction "D-_B7") (pintype "passive"))
    )
    (net (code "45") (name "/USB-PWR-DP") (class "Default")
      (node (ref "U2") (pin "4") (pinfunction "D+_4") (pintype "passive"))
      (node (ref "USB1") (pin "A6") (pinfunction "D+_A6") (pintype "passive"))
      (node (ref "USB1") (pin "B6") (pinfunction "D+_B6") (pintype "passive"))
    )
    (net (code "46") (name "/sw_d0") (class "Default")
      (node (ref "P3") (pin "4") (pinfunction "4_4") (pintype "passive"))
      (node (ref "R17") (pin "2") (pinfunction "2_2") (pintype "passive"))
      (node (ref "U7") (pin "3") (pinfunction "D0_3") (pintype "passive"))
    )
    (net (code "47") (name "/sw_d1") (class "Default")
      (node (ref "P3") (pin "5") (pinfunction "5_5") (pintype "passive"))
      (node (ref "R19") (pin "2") (pinfunction "2_2") (pintype "passive"))
      (node (ref "U7") (pin "6") (pinfunction "D1_6") (pintype "passive"))
    )
    (net (code "48") (name "/sw_d2") (class "Default")
      (node (ref "P3") (pin "6") (pinfunction "6_6") (pintype "passive"))
      (node (ref "R20") (pin "2") (pinfunction "2_2") (pintype "passive"))
      (node (ref "U7") (pin "4") (pinfunction "D2_4") (pintype "passive"))
    )
    (net (code "49") (name "/sw_d3") (class "Default")
      (node (ref "P3") (pin "7") (pinfunction "7_7") (pintype "passive"))
      (node (ref "R18") (pin "2") (pinfunction "2_2") (pintype "passive"))
      (node (ref "U7") (pin "5") (pinfunction "D3_5") (pintype "passive"))
    )
    (net (code "50") (name "/sw_data") (class "Default")
      (node (ref "P3") (pin "2") (pinfunction "2_2") (pintype "passive"))
      (node (ref "U5") (pin "5") (pinfunction "DOUT_5") (pintype "passive"))
      (node (ref "U7") (pin "2") (pinfunction "DATA_2") (pintype "passive"))
    )
    (net (code "51") (name "/sw_vt") (class "Default")
      (node (ref "D1") (pin "1") (pinfunction "A_1") (pintype "passive"))
      (node (ref "P3") (pin "3") (pinfunction "3_3") (pintype "passive"))
      (node (ref "R6") (pin "1") (pinfunction "1_1") (pintype "passive"))
      (node (ref "R7") (pin "2") (pinfunction "2_2") (pintype "passive"))
      (node (ref "U7") (pin "7") (pinfunction "VT_7") (pintype "passive"))
    )
    (net (code "52") (name "3V3") (class "Default")
      (node (ref "C1") (pin "2") (pinfunction "2_2") (pintype "passive"))
      (node (ref "C13") (pin "1") (pinfunction "1_1") (pintype "passive"))
      (node (ref "C2") (pin "2") (pinfunction "2_2") (pintype "passive"))
      (node (ref "C6") (pin "2") (pinfunction "2_2") (pintype "passive"))
      (node (ref "P3") (pin "1") (pinfunction "1_1") (pintype "passive"))
      (node (ref "R14") (pin "2") (pinfunction "2_2") (pintype "passive"))
      (node (ref "R5") (pin "1") (pinfunction "1_1") (pintype "passive"))
      (node (ref "S1") (pin "2") (pinfunction "2_2") (pintype "passive"))
      (node (ref "TP_3V3") (pin "1") (pinfunction "1_1") (pintype "passive"))
      (node (ref "U4") (pin "5") (pinfunction "VOUT_5") (pintype "passive"))
      (node (ref "U5") (pin "3") (pinfunction "VDD_3") (pintype "passive"))
      (node (ref "U6") (pin "1") (pinfunction "VDDA_1") (pintype "power_in"))
      (node (ref "U6") (pin "19") (pinfunction "VDD3P3_RTC_19") (pintype "power_in"))
      (node (ref "U6") (pin "3") (pinfunction "VDD3P3_3") (pintype "power_in"))
      (node (ref "U6") (pin "37") (pinfunction "VDD3P3_CPU_37") (pintype "power_in"))
      (node (ref "U6") (pin "4") (pinfunction "VDD3P3_4") (pintype "power_in"))
      (node (ref "U6") (pin "43") (pinfunction "VDDA_43") (pintype "power_in"))
      (node (ref "U6") (pin "46") (pinfunction "VDDA_46") (pintype "power_in"))
      (node (ref "U7") (pin "1") (pinfunction "VDD_1") (pintype "passive"))
    )
    (net (code "53") (name "300V") (class "Default")
      (node (ref "C14") (pin "1") (pinfunction "1_1") (pintype "passive"))
      (node (ref "C15") (pin "1") (pinfunction "1_1") (pintype "passive"))
      (node (ref "C3") (pin "1") (pinfunction "1_1") (pintype "passive"))
      (node (ref "L1") (pin "1") (pinfunction "1_1") (pintype "passive"))
      (node (ref "P5") (pin "1") (pinfunction "1_1") (pintype "passive"))
      (node (ref "R12") (pin "2") (pinfunction "2_2") (pintype "passive"))
      (node (ref "R21") (pin "2") (pinfunction "2_2") (pintype "passive"))
      (node (ref "R22") (pin "2") (pinfunction "2_2") (pintype "passive"))
      (node (ref "TP_300V") (pin "1") (pinfunction "1_1") (pintype "passive"))
      (node (ref "U1") (pin "1") (pinfunction "+Vo_1") (pintype "passive"))
      (node (ref "U8") (pin "4") (pinfunction "HV_4") (pintype "passive"))
    )
    (net (code "54") (name "GND") (class "Default")
      (node (ref "C1") (pin "1") (pinfunction "1_1") (pintype "passive"))
      (node (ref "C10") (pin "1") (pinfunction "1_1") (pintype "passive"))
      (node (ref "C11") (pin "2") (pinfunction "2_2") (pintype "passive"))
      (node (ref "C12") (pin "1") (pinfunction "1_1") (pintype "passive"))
      (node (ref "C13") (pin "2") (pinfunction "2_2") (pintype "passive"))
      (node (ref "C15") (pin "2") (pinfunction "2_2") (pintype "passive"))
      (node (ref "C16") (pin "2") (pinfunction "2_2") (pintype "passive"))
      (node (ref "C2") (pin "1") (pinfunction "1_1") (pintype "passive"))
      (node (ref "C3") (pin "2") (pinfunction "2_2") (pintype "passive"))
      (node (ref "C4") (pin "2") (pinfunction "2_2") (pintype "passive"))
      (node (ref "C5") (pin "2") (pinfunction "2_2") (pintype "passive"))
      (node (ref "C6") (pin "1") (pinfunction "1_1") (pintype "passive"))
      (node (ref "C7") (pin "1") (pinfunction "1_1") (pintype "passive"))
      (node (ref "C8") (pin "2") (pinfunction "2_2") (pintype "passive"))
      (node (ref "D38") (pin "2") (pinfunction "K_2") (pintype "passive"))
      (node (ref "D39") (pin "2") (pinfunction "K_2") (pintype "passive"))
      (node (ref "D40") (pin "2") (pinfunction "K_2") (pintype "passive"))
      (node (ref "L3") (pin "1") (pinfunction "1_1") (pintype "passive"))
      (node (ref "L4") (pin "1") (pinfunction "1_1") (pintype "passive"))
      (node (ref "P2") (pin "4") (pinfunction "4_4") (pintype "passive"))
      (node (ref "P3") (pin "8") (pinfunction "8_8") (pintype "passive"))
      (node (ref "P4") (pin "2") (pinfunction "2_2") (pintype "passive"))
      (node (ref "P5") (pin "6") (pinfunction "6_6") (pintype "passive"))
      (node (ref "R10") (pin "1") (pinfunction "1_1") (pintype "passive"))
      (node (ref "R13") (pin "2") (pinfunction "2_2") (pintype "passive"))
      (node (ref "R16") (pin "2") (pinfunction "2_2") (pintype "passive"))
      (node (ref "R23") (pin "1") (pinfunction "1_1") (pintype "passive"))
      (node (ref "R24") (pin "1") (pinfunction "1_1") (pintype "passive"))
      (node (ref "R25") (pin "1") (pinfunction "1_1") (pintype "passive"))
      (node (ref "R6") (pin "2") (pinfunction "2_2") (pintype "passive"))
      (node (ref "R8") (pin "1") (pinfunction "1_1") (pintype "passive"))
      (node (ref "R9") (pin "1") (pinfunction "1_1") (pintype "passive"))
      (node (ref "TP_300V") (pin "2") (pinfunction "2_2") (pintype "passive"))
      (node (ref "TP_3V3") (pin "2") (pinfunction "2_2") (pintype "passive"))
      (node (ref "U1") (pin "2") (pinfunction "-Vo_2") (pintype "passive"))
      (node (ref "U2") (pin "29") (pinfunction "HEAT_TAB_29") (pintype "passive"))
      (node (ref "U2") (pin "3") (pinfunction "GND_3") (pintype "passive"))
      (node (ref "U3") (pin "2") (pinfunction "GND_2") (pintype "passive"))
      (node (ref "U4") (pin "2") (pinfunction "GND_2") (pintype "passive"))
      (node (ref "U5") (pin "2") (pinfunction "GND_2") (pintype "passive"))
      (node (ref "U5") (pin "4") (pinfunction "SHUT_4") (pintype "passive"))
      (node (ref "U6") (pin "0") (pinfunction "GND_0") (pintype "power_in"))
      (node (ref "U7") (pin "8") (pinfunction "GND_8") (pintype "passive"))
      (node (ref "U8") (pin "2") (pinfunction "GND_2") (pintype "passive"))
      (node (ref "USB1") (pin "1") (pinfunction "SH1_1") (pintype "passive"))
      (node (ref "USB1") (pin "2") (pinfunction "SH2_2") (pintype "passive"))
      (node (ref "USB1") (pin "3") (pinfunction "SH3_3") (pintype "passive"))
      (node (ref "USB1") (pin "4") (pinfunction "SH4_4") (pintype "passive"))
      (node (ref "USB1") (pin "A1") (pinfunction "GND_A1") (pintype "passive"))
      (node (ref "USB1") (pin "A12") (pinfunction "GND_A12") (pintype "passive"))
      (node (ref "USB1") (pin "B1") (pinfunction "GND_B1") (pintype "passive"))
      (node (ref "USB1") (pin "B12") (pinfunction "GND_B12") (pintype "passive"))
      (node (ref "Y1") (pin "2") (pinfunction "2_2") (pintype "passive"))
    )
    (net (code "55") (name "Net-(A2-Pad1)") (class "Default")
      (node (ref "A2") (pin "1") (pinfunction "1_1") (pintype "passive"))
      (node (ref "C11") (pin "1") (pinfunction "1_1") (pintype "passive"))
      (node (ref "C9") (pin "1") (pinfunction "1_1") (pintype "passive"))
      (node (ref "L3") (pin "2") (pinfunction "2_2") (pintype "passive"))
    )
    (net (code "56") (name "Net-(D1-K)") (class "Default")
      (node (ref "D1") (pin "2") (pinfunction "K_2") (pintype "passive"))
      (node (ref "R16") (pin "1") (pinfunction "1_1") (pintype "passive"))
    )
    (net (code "57") (name "Net-(D2-K)") (class "Default")
      (node (ref "D2") (pin "2") (pinfunction "K_2") (pintype "passive"))
      (node (ref "D3") (pin "1") (pinfunction "A_1") (pintype "passive"))
    )
    (net (code "58") (name "Net-(D3-K)") (class "Default")
      (node (ref "D3") (pin "2") (pinfunction "K_2") (pintype "passive"))
      (node (ref "D4") (pin "1") (pinfunction "A_1") (pintype "passive"))
    )
    (net (code "59") (name "Net-(D4-K)") (class "Default")
      (node (ref "D4") (pin "2") (pinfunction "K_2") (pintype "passive"))
      (node (ref "D5") (pin "1") (pinfunction "A_1") (pintype "passive"))
    )
    (net (code "60") (name "Net-(D5-K)") (class "Default")
      (node (ref "D5") (pin "2") (pinfunction "K_2") (pintype "passive"))
      (node (ref "D6") (pin "1") (pinfunction "A_1") (pintype "passive"))
    )
    (net (code "61") (name "Net-(D6-K)") (class "Default")
      (node (ref "D6") (pin "2") (pinfunction "K_2") (pintype "passive"))
      (node (ref "D7") (pin "1") (pinfunction "A_1") (pintype "passive"))
    )
    (net (code "62") (name "Net-(D7-K)") (class "Default")
      (node (ref "D7") (pin "2") (pinfunction "K_2") (pintype "passive"))
      (node (ref "D8") (pin "1") (pinfunction "A_1") (pintype "passive"))
    )
    (net (code "63") (name "Net-(D8-K)") (class "Default")
      (node (ref "D8") (pin "2") (pinfunction "K_2") (pintype "passive"))
      (node (ref "D9") (pin "1") (pinfunction "A_1") (pintype "passive"))
    )
    (net (code "64") (name "Net-(D10-A)") (class "Default")
      (node (ref "D10") (pin "1") (pinfunction "A_1") (pintype "passive"))
      (node (ref "D9") (pin "2") (pinfunction "K_2") (pintype "passive"))
    )
    (net (code "65") (name "Net-(D10-K)") (class "Default")
      (node (ref "D10") (pin "2") (pinfunction "K_2") (pintype "passive"))
      (node (ref "D11") (pin "1") (pinfunction "A_1") (pintype "passive"))
    )
    (net (code "66") (name "Net-(D11-K)") (class "Default")
      (node (ref "D11") (pin "2") (pinfunction "K_2") (pintype "passive"))
      (node (ref "D12") (pin "1") (pinfunction "A_1") (pintype "passive"))
    )
    (net (code "67") (name "Net-(D12-K)") (class "Default")
      (node (ref "D12") (pin "2") (pinfunction "K_2") (pintype "passive"))
      (node (ref "D13") (pin "1") (pinfunction "A_1") (pintype "passive"))
    )
    (net (code "68") (name "Net-(D13-K)") (class "Default")
      (node (ref "D13") (pin "2") (pinfunction "K_2") (pintype "passive"))
      (node (ref "D14") (pin "1") (pinfunction "A_1") (pintype "passive"))
    )
    (net (code "69") (name "Net-(D14-K)") (class "Default")
      (node (ref "D14") (pin "2") (pinfunction "K_2") (pintype "passive"))
      (node (ref "D15") (pin "1") (pinfunction "A_1") (pintype "passive"))
    )
    (net (code "70") (name "Net-(D15-K)") (class "Default")
      (node (ref "D15") (pin "2") (pinfunction "K_2") (pintype "passive"))
      (node (ref "D16") (pin "1") (pinfunction "A_1") (pintype "passive"))
    )
    (net (code "71") (name "Net-(D16-K)") (class "Default")
      (node (ref "D16") (pin "2") (pinfunction "K_2") (pintype "passive"))
      (node (ref "D17") (pin "1") (pinfunction "A_1") (pintype "passive"))
    )
    (net (code "72") (name "Net-(D17-K)") (class "Default")
      (node (ref "D17") (pin "2") (pinfunction "K_2") (pintype "passive"))
      (node (ref "D18") (pin "1") (pinfunction "A_1") (pintype "passive"))
    )
    (net (code "73") (name "Net-(D18-K)") (class "Default")
      (node (ref "D18") (pin "2") (pinfunction "K_2") (pintype "passive"))
      (node (ref "D19") (pin "1") (pinfunction "A_1") (pintype "passive"))
    )
    (net (code "74") (name "Net-(D19-K)") (class "Default")
      (node (ref "D19") (pin "2") (pinfunction "K_2") (pintype "passive"))
      (node (ref "D20") (pin "1") (pinfunction "A_1") (pintype "passive"))
    )
    (net (code "75") (name "Net-(D20-K)") (class "Default")
      (node (ref "D20") (pin "2") (pinfunction "K_2") (pintype "passive"))
      (node (ref "D21") (pin "1") (pinfunction "A_1") (pintype "passive"))
    )
    (net (code "76") (name "Net-(D21-K)") (class "Default")
      (node (ref "D21") (pin "2") (pinfunction "K_2") (pintype "passive"))
      (node (ref "D22") (pin "1") (pinfunction "A_1") (pintype "passive"))
    )
    (net (code "77") (name "Net-(D22-K)") (class "Default")
      (node (ref "D22") (pin "2") (pinfunction "K_2") (pintype "passive"))
      (node (ref "D23") (pin "1") (pinfunction "A_1") (pintype "passive"))
    )
    (net (code "78") (name "Net-(D23-K)") (class "Default")
      (node (ref "D23") (pin "2") (pinfunction "K_2") (pintype "passive"))
      (node (ref "D24") (pin "1") (pinfunction "A_1") (pintype "passive"))
    )
    (net (code "79") (name "Net-(D24-K)") (class "Default")
      (node (ref "D24") (pin "2") (pinfunction "K_2") (pintype "passive"))
      (node (ref "D25") (pin "1") (pinfunction "A_1") (pintype "passive"))
    )
    (net (code "80") (name "Net-(D25-K)") (class "Default")
      (node (ref "D25") (pin "2") (pinfunction "K_2") (pintype "passive"))
      (node (ref "D26") (pin "1") (pinfunction "A_1") (pintype "passive"))
    )
    (net (code "81") (name "Net-(D26-K)") (class "Default")
      (node (ref "D26") (pin "2") (pinfunction "K_2") (pintype "passive"))
      (node (ref "D27") (pin "1") (pinfunction "A_1") (pintype "passive"))
    )
    (net (code "82") (name "Net-(D27-K)") (class "Default")
      (node (ref "D27") (pin "2") (pinfunction "K_2") (pintype "passive"))
      (node (ref "D28") (pin "1") (pinfunction "A_1") (pintype "passive"))
    )
    (net (code "83") (name "Net-(D28-K)") (class "Default")
      (node (ref "D28") (pin "2") (pinfunction "K_2") (pintype "passive"))
      (node (ref "D29") (pin "1") (pinfunction "A_1") (pintype "passive"))
    )
    (net (code "84") (name "Net-(D29-K)") (class "Default")
      (node (ref "D29") (pin "2") (pinfunction "K_2") (pintype "passive"))
      (node (ref "D30") (pin "1") (pinfunction "A_1") (pintype "passive"))
    )
    (net (code "85") (name "Net-(D30-K)") (class "Default")
      (node (ref "D30") (pin "2") (pinfunction "K_2") (pintype "passive"))
      (node (ref "D31") (pin "1") (pinfunction "A_1") (pintype "passive"))
    )
    (net (code "86") (name "Net-(D31-K)") (class "Default")
      (node (ref "D31") (pin "2") (pinfunction "K_2") (pintype "passive"))
      (node (ref "D32") (pin "1") (pinfunction "A_1") (pintype "passive"))
    )
    (net (code "87") (name "Net-(D32-K)") (class "Default")
      (node (ref "D32") (pin "2") (pinfunction "K_2") (pintype "passive"))
      (node (ref "D33") (pin "1") (pinfunction "A_1") (pintype "passive"))
    )
    (net (code "88") (name "Net-(D33-K)") (class "Default")
      (node (ref "D33") (pin "2") (pinfunction "K_2") (pintype "passive"))
      (node (ref "D34") (pin "1") (pinfunction "A_1") (pintype "passive"))
    )
    (net (code "89") (name "Net-(D34-K)") (class "Default")
      (node (ref "D34") (pin "2") (pinfunction "K_2") (pintype "passive"))
      (node (ref "D35") (pin "1") (pinfunction "A_1") (pintype "passive"))
    )
    (net (code "90") (name "Net-(D35-K)") (class "Default")
      (node (ref "D35") (pin "2") (pinfunction "K_2") (pintype "passive"))
      (node (ref "D36") (pin "1") (pinfunction "A_1") (pintype "passive"))
    )
    (net (code "91") (name "Net-(D36-K)") (class "Default")
      (node (ref "D36") (pin "2") (pinfunction "K_2") (pintype "passive"))
      (node (ref "D37") (pin "1") (pinfunction "A_1") (pintype "passive"))
    )
    (net (code "92") (name "Net-(D38-A)") (class "Default")
      (node (ref "D38") (pin "1") (pinfunction "A_1") (pintype "passive"))
      (node (ref "R12") (pin "1") (pinfunction "1_1") (pintype "passive"))
    )
    (net (code "93") (name "Net-(D39-A)") (class "Default")
      (node (ref "D39") (pin "1") (pinfunction "A_1") (pintype "passive"))
      (node (ref "R14") (pin "1") (pinfunction "1_1") (pintype "passive"))
    )
    (net (code "94") (name "Net-(D40-A)") (class "Default")
      (node (ref "D40") (pin "1") (pinfunction "A_1") (pintype "passive"))
      (node (ref "R15") (pin "1") (pinfunction "1_1") (pintype "passive"))
    )
    (net (code "95") (name "Net-(D41-K)") (class "Default")
      (node (ref "D41") (pin "2") (pinfunction "K_2") (pintype "passive"))
      (node (ref "R25") (pin "2") (pinfunction "2_2") (pintype "passive"))
    )
    (net (code "96") (name "Net-(P1-Pad1)") (class "Default")
      (node (ref "P1") (pin "1") (pinfunction "1_1") (pintype "passive"))
      (node (ref "U1") (pin "4") (pinfunction "AC_4") (pintype "passive"))
    )
    (net (code "97") (name "Net-(P1-Pad2)") (class "Default")
      (node (ref "P1") (pin "2") (pinfunction "2_2") (pintype "passive"))
      (node (ref "U1") (pin "3") (pinfunction "AC_3") (pintype "passive"))
    )
    (net (code "98") (name "Net-(Q1-B)") (class "Default")
      (node (ref "Q1") (pin "1") (pinfunction "B_1") (pintype "passive"))
      (node (ref "R3") (pin "2") (pinfunction "2_2") (pintype "passive"))
    )
    (net (code "99") (name "Net-(Q2-B)") (class "Default")
      (node (ref "Q2") (pin "1") (pinfunction "B_1") (pintype "passive"))
      (node (ref "R4") (pin "2") (pinfunction "2_2") (pintype "passive"))
    )
    (net (code "100") (name "Net-(R7-Pad1)") (class "Default")
      (node (ref "R7") (pin "1") (pinfunction "1_1") (pintype "passive"))
      (node (ref "S1") (pin "1") (pinfunction "1_1") (pintype "passive"))
    )
    (net (code "101") (name "Net-(U2-*RST)") (class "Default")
      (node (ref "R1") (pin "2") (pinfunction "2_2") (pintype "passive"))
      (node (ref "U2") (pin "9") (pinfunction "*RST_9") (pintype "passive"))
    )
    (net (code "102") (name "Net-(U2-TXD)") (class "Default")
      (node (ref "R2") (pin "2") (pinfunction "2_2") (pintype "passive"))
      (node (ref "U2") (pin "26") (pinfunction "TXD_26") (pintype "passive"))
    )
    (net (code "103") (name "Net-(U4-BYPASS)") (class "Default")
      (node (ref "C7") (pin "2") (pinfunction "2_2") (pintype "passive"))
      (node (ref "U4") (pin "4") (pinfunction "BYPASS_4") (pintype "passive"))
    )
    (net (code "104") (name "Net-(U5-CAGC)") (class "Default")
      (node (ref "C10") (pin "2") (pinfunction "2_2") (pintype "passive"))
      (node (ref "U5") (pin "7") (pinfunction "CAGC_7") (pintype "passive"))
    )
    (net (code "105") (name "Net-(U5-CTH)") (class "Default")
      (node (ref "C12") (pin "2") (pinfunction "2_2") (pintype "passive"))
      (node (ref "U5") (pin "6") (pinfunction "CTH_6") (pintype "passive"))
    )
    (net (code "106") (name "Net-(U5-RFIN)") (class "Default")
      (node (ref "C9") (pin "2") (pinfunction "2_2") (pintype "passive"))
      (node (ref "L4") (pin "2") (pinfunction "2_2") (pintype "passive"))
      (node (ref "U5") (pin "1") (pinfunction "RFIN_1") (pintype "passive"))
    )
    (net (code "107") (name "Net-(U5-XOSC)") (class "Default")
      (node (ref "U5") (pin "8") (pinfunction "XOSC_8") (pintype "passive"))
      (node (ref "Y1") (pin "1") (pinfunction "1_1") (pintype "passive"))
    )
    (net (code "108") (name "Net-(U6-LNA_IN)") (class "Default")
      (node (ref "A1") (pin "1") (pinfunction "1_1") (pintype "passive"))
      (node (ref "U6") (pin "2") (pinfunction "LNA_IN_2") (pintype "passive"))
    )
    (net (code "109") (name "Net-(U8-DRAIN)") (class "Default")
      (node (ref "L5") (pin "1") (pinfunction "1_1") (pintype "passive"))
      (node (ref "U8") (pin "5") (pinfunction "DRAIN_5") (pintype "passive"))
    )
    (net (code "110") (name "Net-(U8-ROVP)") (class "Default")
      (node (ref "R8") (pin "2") (pinfunction "2_2") (pintype "passive"))
      (node (ref "U8") (pin "1") (pinfunction "ROVP_1") (pintype "passive"))
    )
    (net (code "111") (name "VDD_5V") (class "Default")
      (node (ref "C16") (pin "1") (pinfunction "1_1") (pintype "passive"))
      (node (ref "C5") (pin "1") (pinfunction "1_1") (pintype "passive"))
      (node (ref "L2") (pin "2") (pinfunction "2_2") (pintype "passive"))
      (node (ref "P2") (pin "1") (pinfunction "1_1") (pintype "passive"))
      (node (ref "R1") (pin "1") (pinfunction "1_1") (pintype "passive"))
      (node (ref "R13") (pin "1") (pinfunction "1_1") (pintype "passive"))
      (node (ref "R15") (pin "2") (pinfunction "2_2") (pintype "passive"))
      (node (ref "U2") (pin "7") (pinfunction "REGIN_7") (pintype "passive"))
      (node (ref "U2") (pin "8") (pinfunction "VBUS_8") (pintype "passive"))
      (node (ref "U3") (pin "1") (pinfunction "VOUT_1") (pintype "passive"))
      (node (ref "U4") (pin "1") (pinfunction "VIN_1") (pintype "passive"))
      (node (ref "U4") (pin "3") (pinfunction "ON/OFF_3") (pintype "passive"))
      (node (ref "USB1") (pin "A4") (pinfunction "VBUS_A4") (pintype "passive"))
      (node (ref "USB1") (pin "A9") (pinfunction "VBUS_A9") (pintype "passive"))
      (node (ref "USB1") (pin "B4") (pinfunction "VBUS_B4") (pintype "passive"))
      (node (ref "USB1") (pin "B9") (pinfunction "VBUS_B9") (pintype "passive"))
    )
    (net (code "112") (name "unconnected-(U2-*SUSPEND-Pad11)") (class "Default")
      (node (ref "U2") (pin "11") (pinfunction "*SUSPEND_11") (pintype "passive"))
    )
    (net (code "113") (name "unconnected-(U2-CTS-Pad23)") (class "Default")
      (node (ref "U2") (pin "23") (pinfunction "CTS_23") (pintype "passive"))
    )
    (net (code "114") (name "unconnected-(U2-DCD-Pad1)") (class "Default")
      (node (ref "U2") (pin "1") (pinfunction "DCD_1") (pintype "passive"))
    )
    (net (code "115") (name "unconnected-(U2-DSR-Pad27)") (class "Default")
      (node (ref "U2") (pin "27") (pinfunction "DSR_27") (pintype "passive"))
    )
    (net (code "116") (name "unconnected-(U2-NC-Pad10)") (class "Default")
      (node (ref "U2") (pin "10") (pinfunction "NC_10") (pintype "passive"))
    )
    (net (code "117") (name "unconnected-(U2-NC-Pad13)") (class "Default")
      (node (ref "U2") (pin "13") (pinfunction "NC_13") (pintype "passive"))
    )
    (net (code "118") (name "unconnected-(U2-NC-Pad14)") (class "Default")
      (node (ref "U2") (pin "14") (pinfunction "NC_14") (pintype "passive"))
    )
    (net (code "119") (name "unconnected-(U2-NC-Pad15)") (class "Default")
      (node (ref "U2") (pin "15") (pinfunction "NC_15") (pintype "passive"))
    )
    (net (code "120") (name "unconnected-(U2-NC-Pad16)") (class "Default")
      (node (ref "U2") (pin "16") (pinfunction "NC_16") (pintype "passive"))
    )
    (net (code "121") (name "unconnected-(U2-NC-Pad17)") (class "Default")
      (node (ref "U2") (pin "17") (pinfunction "NC_17") (pintype "passive"))
    )
    (net (code "122") (name "unconnected-(U2-NC-Pad18)") (class "Default")
      (node (ref "U2") (pin "18") (pinfunction "NC_18") (pintype "passive"))
    )
    (net (code "123") (name "unconnected-(U2-NC-Pad19)") (class "Default")
      (node (ref "U2") (pin "19") (pinfunction "NC_19") (pintype "passive"))
    )
    (net (code "124") (name "unconnected-(U2-NC-Pad20)") (class "Default")
      (node (ref "U2") (pin "20") (pinfunction "NC_20") (pintype "passive"))
    )
    (net (code "125") (name "unconnected-(U2-NC-Pad21)") (class "Default")
      (node (ref "U2") (pin "21") (pinfunction "NC_21") (pintype "passive"))
    )
    (net (code "126") (name "unconnected-(U2-NC-Pad22)") (class "Default")
      (node (ref "U2") (pin "22") (pinfunction "NC_22") (pintype "passive"))
    )
    (net (code "127") (name "unconnected-(U2-RI-Pad2)") (class "Default")
      (node (ref "U2") (pin "2") (pinfunction "RI_2") (pintype "passive"))
    )
    (net (code "128") (name "unconnected-(U2-SUSPEND-Pad12)") (class "Default")
      (node (ref "U2") (pin "12") (pinfunction "SUSPEND_12") (pintype "passive"))
    )
    (net (code "129") (name "unconnected-(U2-VDD-Pad6)") (class "Default")
      (node (ref "U2") (pin "6") (pinfunction "VDD_6") (pintype "passive"))
    )
    (net (code "130") (name "unconnected-(U3-FB-Pad8)") (class "Default")
      (node (ref "U3") (pin "8") (pinfunction "FB_8") (pintype "passive"))
    )
    (net (code "131") (name "unconnected-(U3-NC-Pad3)") (class "Default")
      (node (ref "U3") (pin "3") (pinfunction "NC_3") (pintype "passive"))
    )
    (net (code "132") (name "unconnected-(U6-CAP1_NC-Pad48)") (class "Default")
      (node (ref "U6") (pin "48") (pinfunction "CAP1_NC_48") (pintype "passive"))
    )
    (net (code "133") (name "unconnected-(U6-CAP2_NC-Pad47)") (class "Default")
      (node (ref "U6") (pin "47") (pinfunction "CAP2_NC_47") (pintype "passive"))
    )
    (net (code "134") (name "unconnected-(U6-VDD_SDIO_NC-Pad26)") (class "Default")
      (node (ref "U6") (pin "26") (pinfunction "VDD_SDIO_NC_26") (pintype "passive"))
    )
    (net (code "135") (name "unconnected-(U6-XTAL_N_NC-Pad44)") (class "Default")
      (node (ref "U6") (pin "44") (pinfunction "XTAL_N_NC_44") (pintype "passive"))
    )
    (net (code "136") (name "unconnected-(U6-XTAL_P_NC-Pad45)") (class "Default")
      (node (ref "U6") (pin "45") (pinfunction "XTAL_P_NC_45") (pintype "passive"))
    )
    (net (code "137") (name "unconnected-(U8-NC-Pad3)") (class "Default")
      (node (ref "U8") (pin "3") (pinfunction "NC_3") (pintype "passive"))
    )
    (net (code "138") (name "unconnected-(U8-NC-Pad6)") (class "Default")
      (node (ref "U8") (pin "6") (pinfunction "NC_6") (pintype "passive"))
    )
    (net (code "139") (name "unconnected-(USB1-CC1-PadA5)") (class "Default")
      (node (ref "USB1") (pin "A5") (pinfunction "CC1_A5") (pintype "passive"))
    )
    (net (code "140") (name "unconnected-(USB1-CC2-PadB5)") (class "Default")
      (node (ref "USB1") (pin "B5") (pinfunction "CC2_B5") (pintype "passive"))
    )
    (net (code "141") (name "unconnected-(USB1-RX1+-PadB11)") (class "Default")
      (node (ref "USB1") (pin "B11") (pinfunction "RX1+_B11") (pintype "passive"))
    )
    (net (code "142") (name "unconnected-(USB1-RX1--PadB10)") (class "Default")
      (node (ref "USB1") (pin "B10") (pinfunction "RX1-_B10") (pintype "passive"))
    )
    (net (code "143") (name "unconnected-(USB1-RX2+-PadA11)") (class "Default")
      (node (ref "USB1") (pin "A11") (pinfunction "RX2+_A11") (pintype "passive"))
    )
    (net (code "144") (name "unconnected-(USB1-RX2--PadA10)") (class "Default")
      (node (ref "USB1") (pin "A10") (pinfunction "RX2-_A10") (pintype "passive"))
    )
    (net (code "145") (name "unconnected-(USB1-SBU1-PadA8)") (class "Default")
      (node (ref "USB1") (pin "A8") (pinfunction "SBU1_A8") (pintype "passive"))
    )
    (net (code "146") (name "unconnected-(USB1-SBU2-PadB8)") (class "Default")
      (node (ref "USB1") (pin "B8") (pinfunction "SBU2_B8") (pintype "passive"))
    )
    (net (code "147") (name "unconnected-(USB1-TX1+-PadA2)") (class "Default")
      (node (ref "USB1") (pin "A2") (pinfunction "TX1+_A2") (pintype "passive"))
    )
    (net (code "148") (name "unconnected-(USB1-TX1--PadA3)") (class "Default")
      (node (ref "USB1") (pin "A3") (pinfunction "TX1-_A3") (pintype "passive"))
    )
    (net (code "149") (name "unconnected-(USB1-TX2+-PadB2)") (class "Default")
      (node (ref "USB1") (pin "B2") (pinfunction "TX2+_B2") (pintype "passive"))
    )
    (net (code "150") (name "unconnected-(USB1-TX2--PadB3)") (class "Default")
      (node (ref "USB1") (pin "B3") (pinfunction "TX2-_B3") (pintype "passive"))
    )
  )
)
